# Pg11__USB1.net
KiCad netlist of a schematic drawn in Altium Designer
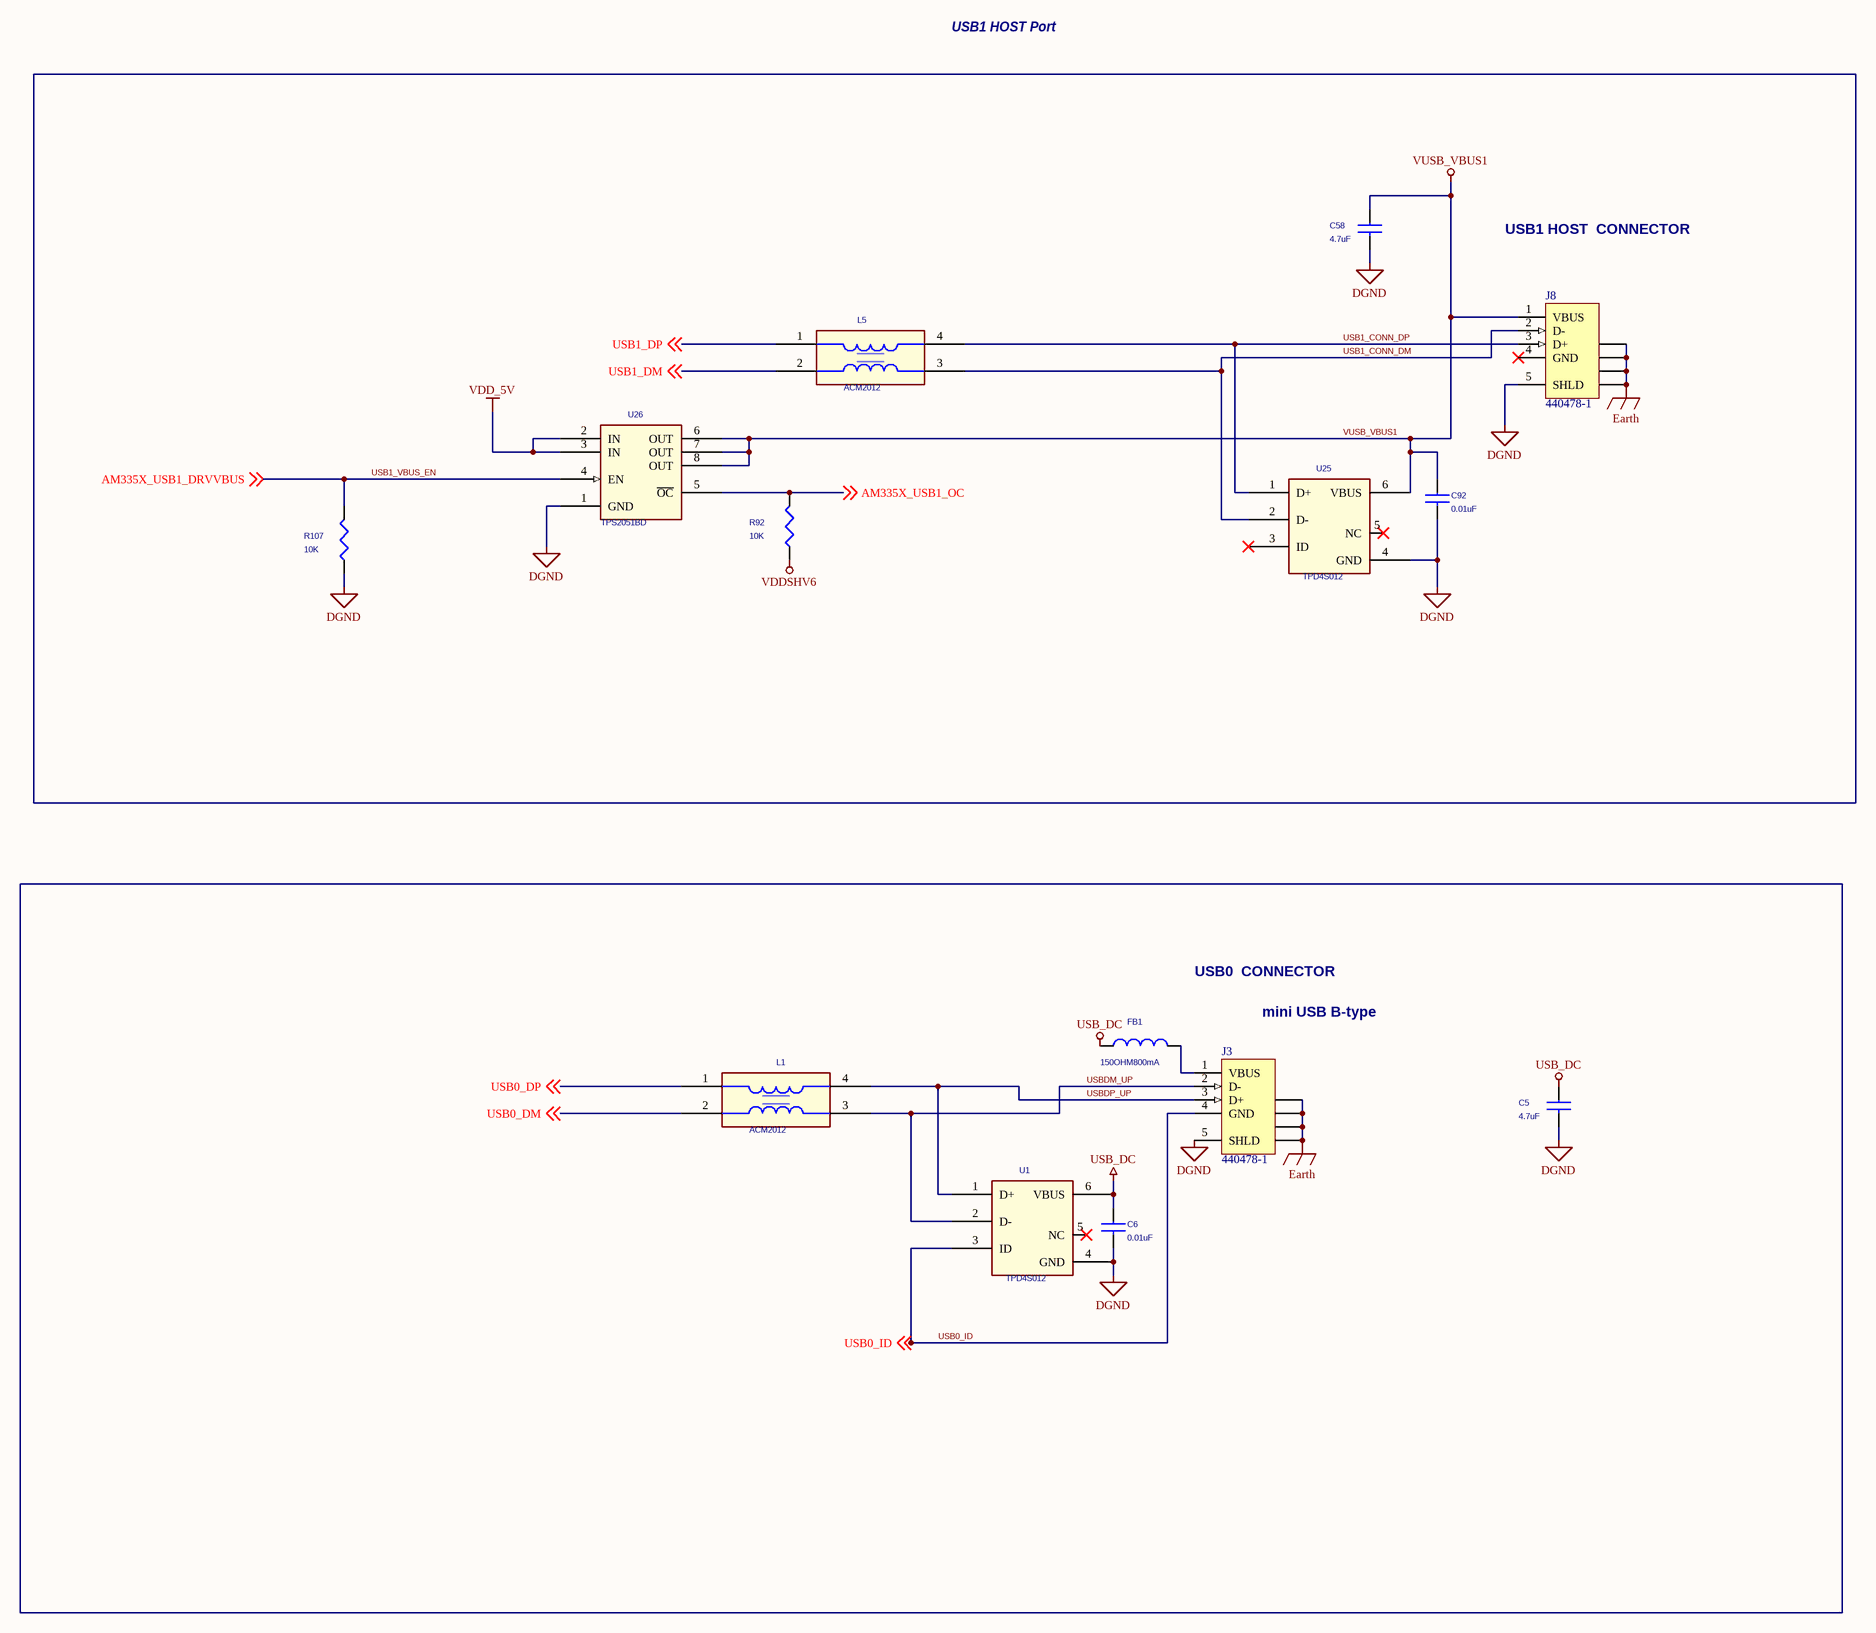
[diagram p0: Pg11_ USB1.SchDoc]

(export (version "E")
  (design (tool "Eeschema 10.0.6"))
  (components
    (comp (ref "C5")
      (value "4.7uF")
      (footprint "SM-7351-CAP-0603")
      (fields (field (name "TIINTPARTNUMBER") "1C0103") (field (name "MFR") "Taiyo Yuden"))
      (libsource (lib "*") (part "4.7uFCapacitor16V10%0603"))
    )
    (comp (ref "C6")
      (value "0.01uF")
      (footprint "SM-7351-CAP-0402")
      (fields (field (name "MFR") "Panasonic") (field (name "TIINTPARTNUMBER") "1C0012"))
      (libsource (lib "*") (part "0.01uFCapacitor16V10%0402_Dup1"))
    )
    (comp (ref "C58")
      (value "4.7uF")
      (footprint "SM-7351-CAP-0603")
      (fields (field (name "TIINTPARTNUMBER") "1C0103") (field (name "MFR") "Taiyo Yuden"))
      (libsource (lib "*") (part "4.7uFCapacitor16V10%0603"))
    )
    (comp (ref "C92")
      (value "0.01uF")
      (footprint "SM-7351-CAP-0402")
      (fields (field (name "MFR") "Panasonic") (field (name "TIINTPARTNUMBER") "1C0012"))
      (libsource (lib "*") (part "0.01uFCapacitor16V10%0402_Dup1"))
    )
    (comp (ref "FB1")
      (value "150OHM800mA")
      (footprint "sm-7351-ind-0805")
      (description "Ferrite Bead 150 Ohm 800mA")
      (fields (field (name "MFR") "Steward") (field (name "TIINTPARTNUMBER") "1L0010"))
      (libsource (lib "*") (part "FerBead_3"))
    )
    (comp (ref "J3")
      (value "440478-1")
      (footprint "ARMflash_mini:440478")
      (description "USB 2.0, Right Angle, SMT, A Type, Receptacle, 5 Position, Black")
      (fields (field (name "PUBLISHER") "Altium Limited"))
      (libsource (lib "ARMflash1a") (part "440478-1"))
    )
    (comp (ref "J8")
      (value "440478-1")
      (footprint "ARMflash_mini:440478")
      (description "USB 2.0, Right Angle, SMT, A Type, Receptacle, 5 Position, Black")
      (fields (field (name "PUBLISHER") "Altium Limited"))
      (libsource (lib "ARMflash1a") (part "440478-1"))
    )
    (comp (ref "L1")
      (value "ACM2012")
      (footprint "ACM2012H")
      (description "Common Mode Filter for USB/HDMI")
      (fields (field (name "TIINTPARTNUMBER") "1M0003") (field (name "MFR") "TDK"))
      (libsource (lib "*") (part "ACM2012"))
    )
    (comp (ref "L5")
      (value "ACM2012")
      (footprint "ACM2012H")
      (description "Common Mode Filter for USB/HDMI")
      (fields (field (name "TIINTPARTNUMBER") "1M0003") (field (name "MFR") "TDK"))
      (libsource (lib "*") (part "ACM2012"))
    )
    (comp (ref "R92")
      (value "10K")
      (footprint "SM-7351-RES-0402")
      (description "Resistor 10Kohm 1/16W 5% 0402")
      (fields (field (name "TIINTPARTNUMBER") "1R0168") (field (name "MFR") "Rohm"))
      (libsource (lib "*") (part "10KOhmResistor1/16W0402_Dup1"))
    )
    (comp (ref "R107")
      (value "10K")
      (footprint "SM-7351-RES-0402")
      (description "Resistor 10Kohm 1/16W 5% 0402")
      (fields (field (name "TIINTPARTNUMBER") "1R0168") (field (name "MFR") "Rohm"))
      (libsource (lib "*") (part "10KOhmResistor1/16W0402_Dup1"))
    )
    (comp (ref "U1")
      (value "TPD4S012")
      (footprint "U_6_DRY")
      (description "ESD 4channel USB Interface")
      (fields (field (name "MFR") "TI") (field (name "TIINTPARTNUMBER") "1A0233"))
      (libsource (lib "*") (part "TPD4S012"))
    )
    (comp (ref "U25")
      (value "TPD4S012")
      (footprint "U_6_DRY")
      (description "ESD 4channel USB Interface")
      (fields (field (name "MFR") "TI") (field (name "TIINTPARTNUMBER") "1A0233"))
      (libsource (lib "*") (part "TPD4S012"))
    )
    (comp (ref "U26")
      (value "TPS2051BD")
      (footprint "U_8_D")
      (description "Power Distribution Switch Current Limited 500mA")
      (fields (field (name "MFR") "TI") (field (name "TIINTPARTNUMBER") "1A0286"))
      (libsource (lib "*") (part "TPS2051BD"))
    )
  )
  (nets
    (net (code "1") (name "/USB1_CONN_DM") (class "Default")
      (node (ref "J8") (pin "2") (pinfunction "D-_2") (pintype "input"))
      (node (ref "L5") (pin "3") (pinfunction "3_3") (pintype "passive"))
      (node (ref "U25") (pin "2") (pinfunction "D-_2") (pintype "passive"))
    )
    (net (code "2") (name "/USB1_CONN_DP") (class "Default")
      (node (ref "J8") (pin "3") (pinfunction "D+_3") (pintype "input"))
      (node (ref "L5") (pin "4") (pinfunction "4_4") (pintype "passive"))
      (node (ref "U25") (pin "1") (pinfunction "D+_1") (pintype "passive"))
    )
    (net (code "3") (name "/USBDM_UP") (class "Default")
      (node (ref "J3") (pin "2") (pinfunction "D-_2") (pintype "input"))
      (node (ref "L1") (pin "3") (pinfunction "3_3") (pintype "passive"))
      (node (ref "U1") (pin "2") (pinfunction "D-_2") (pintype "passive"))
    )
    (net (code "4") (name "/USBDP_UP") (class "Default")
      (node (ref "J3") (pin "3") (pinfunction "D+_3") (pintype "input"))
      (node (ref "L1") (pin "4") (pinfunction "4_4") (pintype "passive"))
      (node (ref "U1") (pin "1") (pinfunction "D+_1") (pintype "passive"))
    )
    (net (code "5") (name "AM335X_USB1_DRVVBUS") (class "Default")
      (node (ref "R107") (pin "1") (pinfunction "P1_1") (pintype "passive"))
      (node (ref "U26") (pin "4") (pinfunction "EN_4") (pintype "input"))
    )
    (net (code "6") (name "AM335X_USB1_OC") (class "Default")
      (node (ref "R92") (pin "1") (pinfunction "P1_1") (pintype "passive"))
      (node (ref "U26") (pin "5") (pinfunction "~{OC}_5") (pintype "open_collector"))
    )
    (net (code "7") (name "DGND") (class "Default")
      (node (ref "C5") (pin "2") (pinfunction "2_2") (pintype "passive"))
      (node (ref "C58") (pin "2") (pinfunction "2_2") (pintype "passive"))
      (node (ref "C6") (pin "2") (pinfunction "2_2") (pintype "passive"))
      (node (ref "C92") (pin "2") (pinfunction "2_2") (pintype "passive"))
      (node (ref "J3") (pin "5") (pinfunction "SHLD_5") (pintype "passive"))
      (node (ref "J8") (pin "5") (pinfunction "SHLD_5") (pintype "passive"))
      (node (ref "R107") (pin "2") (pinfunction "P2_2") (pintype "passive"))
      (node (ref "U1") (pin "4") (pinfunction "GND_4") (pintype "power_in"))
      (node (ref "U25") (pin "4") (pinfunction "GND_4") (pintype "power_in"))
      (node (ref "U26") (pin "1") (pinfunction "GND_1") (pintype "power_in"))
    )
    (net (code "8") (name "Earth") (class "Default")
      (node (ref "J3") (pin "6") (pinfunction "SHLD_6") (pintype "passive"))
      (node (ref "J3") (pin "7") (pinfunction "SHLD_7") (pintype "passive"))
      (node (ref "J3") (pin "8") (pinfunction "SHLD_8") (pintype "passive"))
      (node (ref "J3") (pin "9") (pinfunction "SHLD_9") (pintype "passive"))
      (node (ref "J8") (pin "6") (pinfunction "SHLD_6") (pintype "passive"))
      (node (ref "J8") (pin "7") (pinfunction "SHLD_7") (pintype "passive"))
      (node (ref "J8") (pin "8") (pinfunction "SHLD_8") (pintype "passive"))
      (node (ref "J8") (pin "9") (pinfunction "SHLD_9") (pintype "passive"))
    )
    (net (code "9") (name "Net-(J3-VBUS)") (class "Default")
      (node (ref "FB1") (pin "2") (pinfunction "2_2") (pintype "passive"))
      (node (ref "J3") (pin "1") (pinfunction "VBUS_1") (pintype "power_in"))
    )
    (net (code "10") (name "USB0_DM") (class "Default")
      (node (ref "L1") (pin "2") (pinfunction "2_2") (pintype "passive"))
    )
    (net (code "11") (name "USB0_DP") (class "Default")
      (node (ref "L1") (pin "1") (pinfunction "1_1") (pintype "passive"))
    )
    (net (code "12") (name "USB0_ID") (class "Default")
      (node (ref "J3") (pin "4") (pinfunction "GND_4") (pintype "power_in"))
      (node (ref "U1") (pin "3") (pinfunction "ID_3") (pintype "passive"))
    )
    (net (code "13") (name "USB1_DM") (class "Default")
      (node (ref "L5") (pin "2") (pinfunction "2_2") (pintype "passive"))
    )
    (net (code "14") (name "USB1_DP") (class "Default")
      (node (ref "L5") (pin "1") (pinfunction "1_1") (pintype "passive"))
    )
    (net (code "15") (name "USB_DC") (class "Default")
      (node (ref "C5") (pin "1") (pinfunction "1_1") (pintype "passive"))
      (node (ref "C6") (pin "1") (pinfunction "1_1") (pintype "passive"))
      (node (ref "FB1") (pin "1") (pinfunction "1_1") (pintype "passive"))
      (node (ref "U1") (pin "6") (pinfunction "VBUS_6") (pintype "power_in"))
    )
    (net (code "16") (name "VDDSHV6") (class "Default")
      (node (ref "R92") (pin "2") (pinfunction "P2_2") (pintype "passive"))
    )
    (net (code "17") (name "VDD_5V") (class "Default")
      (node (ref "U26") (pin "2") (pinfunction "IN_2") (pintype "power_in"))
      (node (ref "U26") (pin "3") (pinfunction "IN_3") (pintype "power_in"))
    )
    (net (code "18") (name "VUSB_VBUS1") (class "Default")
      (node (ref "C58") (pin "1") (pinfunction "1_1") (pintype "passive"))
      (node (ref "C92") (pin "1") (pinfunction "1_1") (pintype "passive"))
      (node (ref "J8") (pin "1") (pinfunction "VBUS_1") (pintype "power_in"))
      (node (ref "U25") (pin "6") (pinfunction "VBUS_6") (pintype "power_in"))
      (node (ref "U26") (pin "6") (pinfunction "OUT_6") (pintype "power_in"))
      (node (ref "U26") (pin "7") (pinfunction "OUT_7") (pintype "power_in"))
      (node (ref "U26") (pin "8") (pinfunction "OUT_8") (pintype "power_in"))
    )
    (net (code "19") (name "unconnected-(J8-GND-Pad4)") (class "Default")
      (node (ref "J8") (pin "4") (pinfunction "GND_4") (pintype "power_in+no_connect"))
    )
    (net (code "20") (name "unconnected-(U1-NC-Pad5)") (class "Default")
      (node (ref "U1") (pin "5") (pinfunction "NC_5") (pintype "passive+no_connect"))
    )
    (net (code "21") (name "unconnected-(U25-ID-Pad3)") (class "Default")
      (node (ref "U25") (pin "3") (pinfunction "ID_3") (pintype "passive+no_connect"))
    )
    (net (code "22") (name "unconnected-(U25-NC-Pad5)") (class "Default")
      (node (ref "U25") (pin "5") (pinfunction "NC_5") (pintype "passive+no_connect"))
    )
  )
)
